# Prototipo3.net
KiCad netlist of a schematic drawn in EAGLE
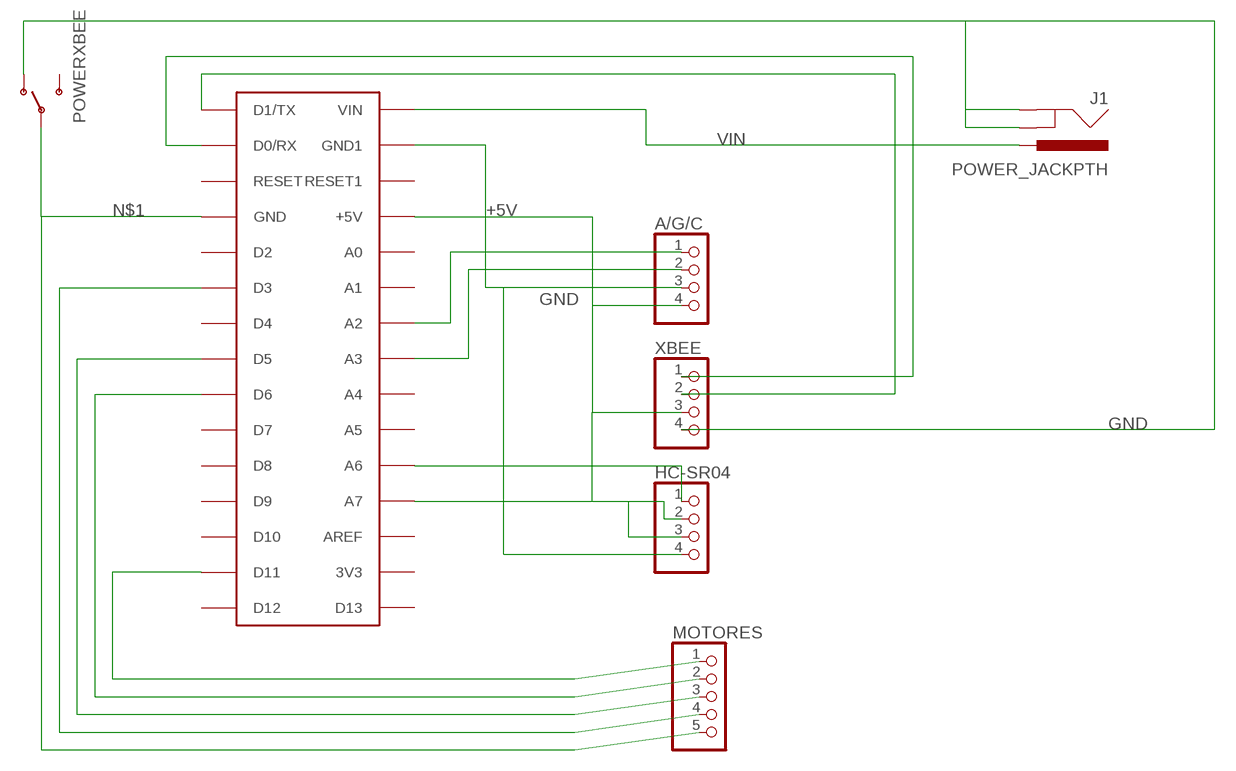
[diagram p0: schematic, sheet 1]

(export (version "E")
  (design (tool "Eeschema 10.0.6"))
  (components
    (comp (ref "A/G/C")
      (value "PINHD-1X4/90")
      (footprint "eagle-import:1X04_90")
      (libsource (lib "eagle-import") (part "PINHD-1X4/90"))
    )
    (comp (ref "HC-SR04")
      (value "PINHD-1X4")
      (footprint "eagle-import:1X04")
      (libsource (lib "eagle-import") (part "PINHD-1X4"))
    )
    (comp (ref "J1")
      (value "POWER_JACKPTH")
      (footprint "eagle-import:POWER_JACK_PTH")
      (libsource (lib "eagle-import") (part "POWER_JACKPTH"))
    )
    (comp (ref "MOTORES")
      (value "PINHD-1X5")
      (footprint "eagle-import:1X05")
      (libsource (lib "eagle-import") (part "PINHD-1X5"))
    )
    (comp (ref "POWERXBEE")
      (value "SWITCH-SPDTPTH")
      (footprint "eagle-import:SWITCH-SPDT")
      (libsource (lib "eagle-import") (part "SWITCH-SPDTPTH"))
    )
    (comp (ref "U$1")
      (value "ARDUINONANO")
      (footprint "eagle-import:PDIP-32")
      (libsource (lib "eagle-import") (part "ARDUINONANO"))
    )
    (comp (ref "XBEE")
      (value "PINHD-1X4")
      (footprint "eagle-import:1X04")
      (libsource (lib "eagle-import") (part "PINHD-1X4"))
    )
  )
  (nets
    (net (code "1") (name "/+5V") (class "Default")
      (node (ref "A/G/C") (pin "4") (pinfunction "4_4") (pintype "passive"))
      (node (ref "HC-SR04") (pin "3") (pinfunction "3_3") (pintype "passive"))
      (node (ref "U$1") (pin "+5V") (pinfunction "+5V_+5V") (pintype "bidirectional"))
      (node (ref "XBEE") (pin "3") (pinfunction "3_3") (pintype "passive"))
    )
    (net (code "2") (name "/GND") (class "Default")
      (node (ref "A/G/C") (pin "3") (pinfunction "3_3") (pintype "passive"))
      (node (ref "HC-SR04") (pin "4") (pinfunction "4_4") (pintype "passive"))
      (node (ref "J1") (pin "GND") (pinfunction "GND_GND") (pintype "bidirectional"))
      (node (ref "J1") (pin "GNDBREAK") (pinfunction "GNDBREAK_GNDBREAK") (pintype "bidirectional"))
      (node (ref "POWERXBEE") (pin "1") (pinfunction "O_1") (pintype "passive"))
      (node (ref "U$1") (pin "GND1") (pinfunction "GND1_GND1") (pintype "bidirectional"))
      (node (ref "XBEE") (pin "4") (pinfunction "4_4") (pintype "passive"))
    )
    (net (code "3") (name "/N$1") (class "Default")
      (node (ref "MOTORES") (pin "5") (pinfunction "5_5") (pintype "passive"))
      (node (ref "POWERXBEE") (pin "2") (pinfunction "P_2") (pintype "passive"))
      (node (ref "U$1") (pin "GND") (pinfunction "GND_GND") (pintype "bidirectional"))
    )
    (net (code "4") (name "/VIN") (class "Default")
      (node (ref "J1") (pin "PWR") (pinfunction "PWR_PWR") (pintype "bidirectional"))
      (node (ref "U$1") (pin "VIN") (pinfunction "VIN_VIN") (pintype "bidirectional"))
    )
    (net (code "5") (name "Net-(A/G/C-Pad1)") (class "Default")
      (node (ref "A/G/C") (pin "1") (pinfunction "1_1") (pintype "passive"))
      (node (ref "U$1") (pin "A2") (pinfunction "A2_A2") (pintype "bidirectional"))
    )
    (net (code "6") (name "Net-(A/G/C-Pad2)") (class "Default")
      (node (ref "A/G/C") (pin "2") (pinfunction "2_2") (pintype "passive"))
      (node (ref "U$1") (pin "A3") (pinfunction "A3_A3") (pintype "bidirectional"))
    )
    (net (code "7") (name "Net-(HC-SR04-Pad1)") (class "Default")
      (node (ref "HC-SR04") (pin "1") (pinfunction "1_1") (pintype "passive"))
      (node (ref "U$1") (pin "A6") (pinfunction "A6_A6") (pintype "bidirectional"))
    )
    (net (code "8") (name "Net-(HC-SR04-Pad2)") (class "Default")
      (node (ref "HC-SR04") (pin "2") (pinfunction "2_2") (pintype "passive"))
      (node (ref "U$1") (pin "A7") (pinfunction "A7_A7") (pintype "bidirectional"))
    )
    (net (code "9") (name "Net-(MOTORES-Pad1)") (class "Default")
      (node (ref "MOTORES") (pin "1") (pinfunction "1_1") (pintype "passive"))
      (node (ref "U$1") (pin "D11") (pinfunction "D11_D11") (pintype "bidirectional"))
    )
    (net (code "10") (name "Net-(MOTORES-Pad2)") (class "Default")
      (node (ref "MOTORES") (pin "2") (pinfunction "2_2") (pintype "passive"))
      (node (ref "U$1") (pin "D6") (pinfunction "D6_D6") (pintype "bidirectional"))
    )
    (net (code "11") (name "Net-(MOTORES-Pad3)") (class "Default")
      (node (ref "MOTORES") (pin "3") (pinfunction "3_3") (pintype "passive"))
      (node (ref "U$1") (pin "D5") (pinfunction "D5_D5") (pintype "bidirectional"))
    )
    (net (code "12") (name "Net-(MOTORES-Pad4)") (class "Default")
      (node (ref "MOTORES") (pin "4") (pinfunction "4_4") (pintype "passive"))
      (node (ref "U$1") (pin "D3") (pinfunction "D3_D3") (pintype "bidirectional"))
    )
    (net (code "13") (name "Net-(U$1-PadD0{slash}RX)") (class "Default")
      (node (ref "U$1") (pin "D0/RX") (pinfunction "D0/RX_D0/RX") (pintype "bidirectional"))
      (node (ref "XBEE") (pin "1") (pinfunction "1_1") (pintype "passive"))
    )
    (net (code "14") (name "Net-(U$1-PadD1{slash}TX)") (class "Default")
      (node (ref "U$1") (pin "D1/TX") (pinfunction "D1/TX_D1/TX") (pintype "bidirectional"))
      (node (ref "XBEE") (pin "2") (pinfunction "2_2") (pintype "passive"))
    )
    (net (code "15") (name "unconnected-(POWERXBEE-S-Pad3)") (class "Default")
      (node (ref "POWERXBEE") (pin "3") (pinfunction "S_3") (pintype "passive"))
    )
    (net (code "16") (name "unconnected-(U$1-Pad3V3)") (class "Default")
      (node (ref "U$1") (pin "3V3") (pinfunction "3V3_3V3") (pintype "bidirectional"))
    )
    (net (code "17") (name "unconnected-(U$1-PadA0)") (class "Default")
      (node (ref "U$1") (pin "A0") (pinfunction "A0_A0") (pintype "bidirectional"))
    )
    (net (code "18") (name "unconnected-(U$1-PadA1)") (class "Default")
      (node (ref "U$1") (pin "A1") (pinfunction "A1_A1") (pintype "bidirectional"))
    )
    (net (code "19") (name "unconnected-(U$1-PadA4)") (class "Default")
      (node (ref "U$1") (pin "A4") (pinfunction "A4_A4") (pintype "bidirectional"))
    )
    (net (code "20") (name "unconnected-(U$1-PadA5)") (class "Default")
      (node (ref "U$1") (pin "A5") (pinfunction "A5_A5") (pintype "bidirectional"))
    )
    (net (code "21") (name "unconnected-(U$1-PadAREF)") (class "Default")
      (node (ref "U$1") (pin "AREF") (pinfunction "AREF_AREF") (pintype "bidirectional"))
    )
    (net (code "22") (name "unconnected-(U$1-PadD2)") (class "Default")
      (node (ref "U$1") (pin "D2") (pinfunction "D2_D2") (pintype "bidirectional"))
    )
    (net (code "23") (name "unconnected-(U$1-PadD4)") (class "Default")
      (node (ref "U$1") (pin "D4") (pinfunction "D4_D4") (pintype "bidirectional"))
    )
    (net (code "24") (name "unconnected-(U$1-PadD7)") (class "Default")
      (node (ref "U$1") (pin "D7") (pinfunction "D7_D7") (pintype "bidirectional"))
    )
    (net (code "25") (name "unconnected-(U$1-PadD8)") (class "Default")
      (node (ref "U$1") (pin "D8") (pinfunction "D8_D8") (pintype "bidirectional"))
    )
    (net (code "26") (name "unconnected-(U$1-PadD9)") (class "Default")
      (node (ref "U$1") (pin "D9") (pinfunction "D9_D9") (pintype "bidirectional"))
    )
    (net (code "27") (name "unconnected-(U$1-PadD10)") (class "Default")
      (node (ref "U$1") (pin "D10") (pinfunction "D10_D10") (pintype "bidirectional"))
    )
    (net (code "28") (name "unconnected-(U$1-PadD12)") (class "Default")
      (node (ref "U$1") (pin "D12") (pinfunction "D12_D12") (pintype "bidirectional"))
    )
    (net (code "29") (name "unconnected-(U$1-PadD13)") (class "Default")
      (node (ref "U$1") (pin "D13") (pinfunction "D13_D13") (pintype "bidirectional"))
    )
    (net (code "30") (name "unconnected-(U$1-PadRESET)") (class "Default")
      (node (ref "U$1") (pin "RESET") (pinfunction "RESET_RESET") (pintype "bidirectional"))
    )
    (net (code "31") (name "unconnected-(U$1-PadRESET1)") (class "Default")
      (node (ref "U$1") (pin "RESET1") (pinfunction "RESET1_RESET1") (pintype "bidirectional"))
    )
  )
)
